# MiniCar_SchDoc.net
KiCad netlist of a schematic drawn in Altium Designer
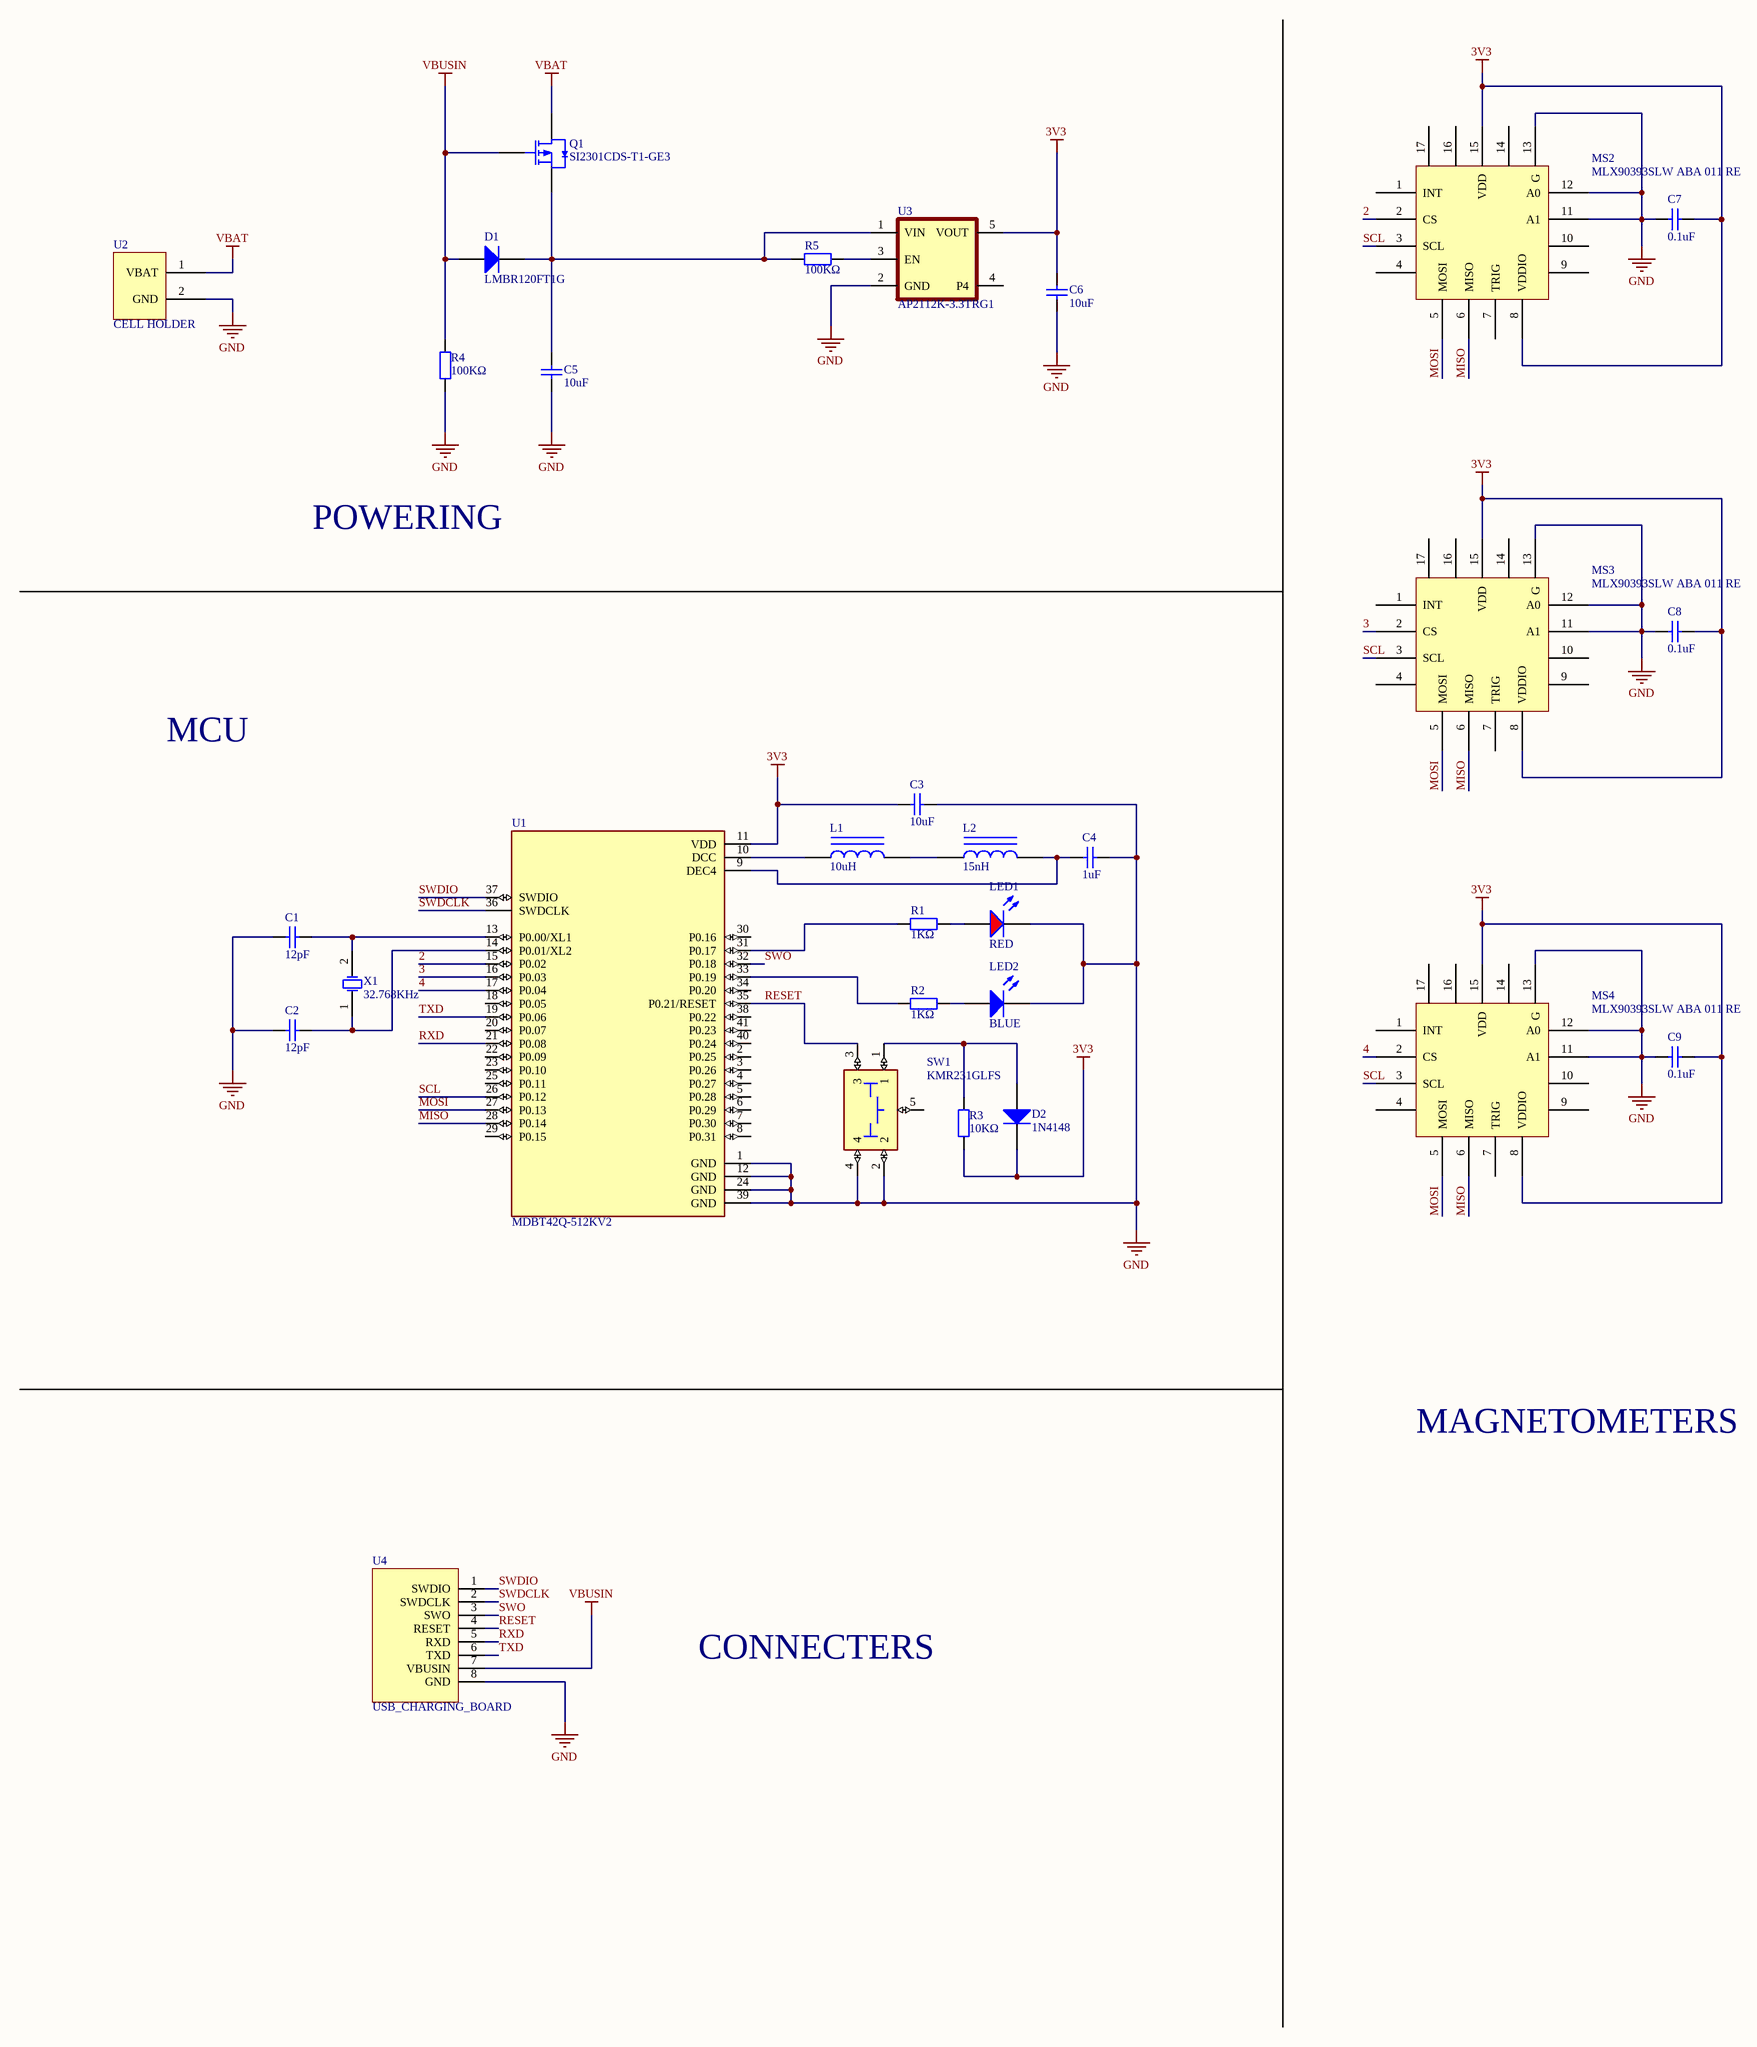
[diagram p0: MiniCar_SchDoc.SchDoc]

(export (version "E")
  (design (tool "Eeschema 10.0.6"))
  (components
    (comp (ref "C1")
      (value "12pF")
      (footprint "0402_C")
      (description "capacitance")
      (libsource (lib "magjoint_MCU") (part "CAP_12pF"))
    )
    (comp (ref "C2")
      (value "12pF")
      (footprint "0402_C")
      (description "capacitance")
      (libsource (lib "magjoint_MCU") (part "CAP_12pF"))
    )
    (comp (ref "C3")
      (value "10uF")
      (footprint "0402_C")
      (description "capacitance")
      (libsource (lib "magjoint_MCU") (part "CAP_10uF"))
    )
    (comp (ref "C4")
      (value "1uF")
      (footprint "0402_C")
      (description "capacitance")
      (libsource (lib "magjoint_MCU") (part "CAP_10uF"))
    )
    (comp (ref "C5")
      (value "10uF")
      (footprint "0402_C")
      (description "capacitance")
      (libsource (lib "magjoint_MCU") (part "CAP_10uF"))
    )
    (comp (ref "C6")
      (value "10uF")
      (footprint "0402_C")
      (description "capacitance")
      (libsource (lib "magjoint_MCU") (part "CAP_10uF"))
    )
    (comp (ref "C7")
      (value "0.1uF")
      (footprint "0402_C")
      (description "capacitance")
      (libsource (lib "magjoint_MCU") (part "CAP_1uF"))
    )
    (comp (ref "C8")
      (value "0.1uF")
      (footprint "0402_C")
      (description "capacitance")
      (libsource (lib "magjoint_MCU") (part "CAP_1uF"))
    )
    (comp (ref "C9")
      (value "0.1uF")
      (footprint "0402_C")
      (description "capacitance")
      (libsource (lib "magjoint_MCU") (part "CAP_1uF"))
    )
    (comp (ref "D1")
      (value "LMBR120FT1G")
      (footprint "SOD-123")
      (description "schottky diode")
      (libsource (lib "magjoint_MCU") (part "DIO_5"))
    )
    (comp (ref "D2")
      (value "1N4148")
      (footprint "SOD-323F")
      (description "diode")
      (libsource (lib "MAGNETO") (part "DIO_4"))
    )
    (comp (ref "L1")
      (value "10uH")
      (footprint "0402_L")
      (description "inductance")
      (libsource (lib "magjoint_MCU") (part "IND_10uH"))
    )
    (comp (ref "L2")
      (value "15nH")
      (footprint "0402_L")
      (description "inductance")
      (libsource (lib "magjoint_MCU") (part "IND_15nH"))
    )
    (comp (ref "LED1")
      (value "RED")
      (footprint "0603_LED_S1")
      (description "LED")
      (libsource (lib "magjoint_MCU") (part "LED_RED"))
    )
    (comp (ref "LED2")
      (value "BLUE")
      (footprint "0603_LED_S1")
      (description "LED")
      (libsource (lib "magjoint_MCU") (part "LED_BLUE"))
    )
    (comp (ref "MS2")
      (value "MLX90393SLW ABA 011 RE")
      (footprint "VQFN-16_EP_3.0x3.0xo.5P")
      (description "sensor")
      (libsource (lib "magjoint_MCU") (part "MLX90393SLW ABA 011 RE"))
    )
    (comp (ref "MS3")
      (value "MLX90393SLW ABA 011 RE")
      (footprint "VQFN-16_EP_3.0x3.0xo.5P")
      (description "sensor")
      (libsource (lib "magjoint_MCU") (part "MLX90393SLW ABA 011 RE"))
    )
    (comp (ref "MS4")
      (value "MLX90393SLW ABA 011 RE")
      (footprint "VQFN-16_EP_3.0x3.0xo.5P")
      (description "sensor")
      (libsource (lib "magjoint_MCU") (part "MLX90393SLW ABA 011 RE"))
    )
    (comp (ref "Q1")
      (value "SI2301CDS-T1-GE3")
      (footprint "SOT-23(SOT-23-3)")
      (description "field effect tube")
      (libsource (lib "magjoint_MCU") (part "MOS"))
    )
    (comp (ref "R1")
      (value "1KΩ")
      (footprint "0402_R")
      (description "resistance")
      (libsource (lib "magjoint_MCU") (part "RES_1KΩ"))
    )
    (comp (ref "R2")
      (value "1KΩ")
      (footprint "0402_R")
      (description "resistance")
      (libsource (lib "magjoint_MCU") (part "RES_1KΩ"))
    )
    (comp (ref "R3")
      (value "10KΩ")
      (footprint "0402_R")
      (description "resistance")
      (libsource (lib "") (part "RES_1KΩ_1"))
    )
    (comp (ref "R4")
      (value "100KΩ")
      (footprint "0402_R")
      (description "resistance")
      (libsource (lib "") (part "RES_100KΩ_1"))
    )
    (comp (ref "R5")
      (value "100KΩ")
      (footprint "0402_R")
      (description "resistance")
      (libsource (lib "magjoint_MCU") (part "RES_100KΩ"))
    )
    (comp (ref "SW1")
      (value "KMR231GLFS")
      (footprint "KMR231GLFS")
      (description "Tactile Switch SPST-NO Top Actuated Surface Mount")
      (libsource (lib "magjoint_MCU") (part "KMR231GLFS"))
    )
    (comp (ref "U1")
      (value "MDBT42Q-512KV2")
      (footprint "SMD_10.0X16.0")
      (libsource (lib "magjoint_MCU") (part "MDBT42Q-512KV2"))
    )
    (comp (ref "U2")
      (value "CELL HOLDER")
      (footprint "BAT_MX 1.25-WI-2P")
      (description "button cell battary holder BS-08-B2AA025")
      (libsource (lib "magjoint_MCU") (part "BAT"))
    )
    (comp (ref "U3")
      (value "AP2112K-3.3TRG1")
      (footprint "SOT95P285X140-5N")
      (description "LDO_ low dropout linear regulator")
      (libsource (lib "magjoint_MCU") (part "AP2112K"))
    )
    (comp (ref "U4")
      (value "USB_CHARGING_BOARD")
      (footprint "FPC0.5 2H-WS-8P")
      (libsource (lib "magjoint_MCU") (part "USB_CHARGING_BOARD"))
    )
    (comp (ref "X1")
      (value "32.768KHz")
      (footprint "SMD-3215_2P FC - 135")
      (description "crystal")
      (libsource (lib "magjoint_MCU") (part "ABS07-32.768KHZ-7-T"))
    )
  )
  (nets
    (net (code "1") (name "/2") (class "Default")
      (node (ref "MS2") (pin "2") (pinfunction "CS_2") (pintype "passive"))
      (node (ref "U1") (pin "15") (pinfunction "P0.02_15") (pintype "bidirectional"))
    )
    (net (code "2") (name "/3") (class "Default")
      (node (ref "MS3") (pin "2") (pinfunction "CS_2") (pintype "passive"))
      (node (ref "U1") (pin "16") (pinfunction "P0.03_16") (pintype "bidirectional"))
    )
    (net (code "3") (name "/4") (class "Default")
      (node (ref "MS4") (pin "2") (pinfunction "CS_2") (pintype "passive"))
      (node (ref "U1") (pin "17") (pinfunction "P0.04_17") (pintype "bidirectional"))
    )
    (net (code "4") (name "/MISO") (class "Default")
      (node (ref "MS2") (pin "6") (pinfunction "MISO_6") (pintype "passive"))
      (node (ref "MS3") (pin "6") (pinfunction "MISO_6") (pintype "passive"))
      (node (ref "MS4") (pin "6") (pinfunction "MISO_6") (pintype "passive"))
      (node (ref "U1") (pin "28") (pinfunction "P0.14_28") (pintype "bidirectional"))
    )
    (net (code "5") (name "/MOSI") (class "Default")
      (node (ref "MS2") (pin "5") (pinfunction "MOSI_5") (pintype "passive"))
      (node (ref "MS3") (pin "5") (pinfunction "MOSI_5") (pintype "passive"))
      (node (ref "MS4") (pin "5") (pinfunction "MOSI_5") (pintype "passive"))
      (node (ref "U1") (pin "27") (pinfunction "P0.13_27") (pintype "bidirectional"))
    )
    (net (code "6") (name "/RESET") (class "Default")
      (node (ref "SW1") (pin "3") (pinfunction "3_3") (pintype "bidirectional"))
      (node (ref "U1") (pin "35") (pinfunction "P0.21/RESET_35") (pintype "bidirectional"))
      (node (ref "U4") (pin "4") (pinfunction "RESET_4") (pintype "passive"))
    )
    (net (code "7") (name "/RXD") (class "Default")
      (node (ref "U1") (pin "21") (pinfunction "P0.08_21") (pintype "bidirectional"))
      (node (ref "U4") (pin "5") (pinfunction "RXD_5") (pintype "passive"))
    )
    (net (code "8") (name "/SCL") (class "Default")
      (node (ref "MS2") (pin "3") (pinfunction "SCL_3") (pintype "passive"))
      (node (ref "MS3") (pin "3") (pinfunction "SCL_3") (pintype "passive"))
      (node (ref "MS4") (pin "3") (pinfunction "SCL_3") (pintype "passive"))
      (node (ref "U1") (pin "26") (pinfunction "P0.12_26") (pintype "bidirectional"))
    )
    (net (code "9") (name "/SWDCLK") (class "Default")
      (node (ref "U1") (pin "36") (pinfunction "SWDCLK_36") (pintype "power_in"))
      (node (ref "U4") (pin "2") (pinfunction "SWDCLK_2") (pintype "passive"))
    )
    (net (code "10") (name "/SWDIO") (class "Default")
      (node (ref "U1") (pin "37") (pinfunction "SWDIO_37") (pintype "bidirectional"))
      (node (ref "U4") (pin "1") (pinfunction "SWDIO_1") (pintype "passive"))
    )
    (net (code "11") (name "/SWO") (class "Default")
      (node (ref "U1") (pin "32") (pinfunction "P0.18_32") (pintype "bidirectional"))
      (node (ref "U4") (pin "3") (pinfunction "SWO_3") (pintype "passive"))
    )
    (net (code "12") (name "/TXD") (class "Default")
      (node (ref "U1") (pin "19") (pinfunction "P0.06_19") (pintype "bidirectional"))
      (node (ref "U4") (pin "6") (pinfunction "TXD_6") (pintype "passive"))
    )
    (net (code "13") (name "3V3") (class "Default")
      (node (ref "C3") (pin "1") (pinfunction "1_1") (pintype "passive"))
      (node (ref "C6") (pin "2") (pinfunction "2_2") (pintype "passive"))
      (node (ref "C7") (pin "2") (pinfunction "2_2") (pintype "passive"))
      (node (ref "C8") (pin "2") (pinfunction "2_2") (pintype "passive"))
      (node (ref "C9") (pin "2") (pinfunction "2_2") (pintype "passive"))
      (node (ref "D2") (pin "2") (pinfunction "K_2") (pintype "passive"))
      (node (ref "MS2") (pin "15") (pinfunction "VDD_15") (pintype "passive"))
      (node (ref "MS2") (pin "8") (pinfunction "VDDIO_8") (pintype "passive"))
      (node (ref "MS3") (pin "15") (pinfunction "VDD_15") (pintype "passive"))
      (node (ref "MS3") (pin "8") (pinfunction "VDDIO_8") (pintype "passive"))
      (node (ref "MS4") (pin "15") (pinfunction "VDD_15") (pintype "passive"))
      (node (ref "MS4") (pin "8") (pinfunction "VDDIO_8") (pintype "passive"))
      (node (ref "R3") (pin "1") (pinfunction "1_1") (pintype "passive"))
      (node (ref "U1") (pin "11") (pinfunction "VDD_11") (pintype "power_in"))
      (node (ref "U3") (pin "5") (pinfunction "VOUT_5") (pintype "power_in"))
    )
    (net (code "14") (name "GND") (class "Default")
      (node (ref "C1") (pin "1") (pinfunction "1_1") (pintype "passive"))
      (node (ref "C2") (pin "1") (pinfunction "1_1") (pintype "passive"))
      (node (ref "C3") (pin "2") (pinfunction "2_2") (pintype "passive"))
      (node (ref "C4") (pin "2") (pinfunction "2_2") (pintype "passive"))
      (node (ref "C5") (pin "1") (pinfunction "1_1") (pintype "passive"))
      (node (ref "C6") (pin "1") (pinfunction "1_1") (pintype "passive"))
      (node (ref "C7") (pin "1") (pinfunction "1_1") (pintype "passive"))
      (node (ref "C8") (pin "1") (pinfunction "1_1") (pintype "passive"))
      (node (ref "C9") (pin "1") (pinfunction "1_1") (pintype "passive"))
      (node (ref "LED1") (pin "K") (pinfunction "K_K") (pintype "passive"))
      (node (ref "LED2") (pin "K") (pinfunction "K_K") (pintype "passive"))
      (node (ref "MS2") (pin "11") (pinfunction "A1_11") (pintype "passive"))
      (node (ref "MS2") (pin "12") (pinfunction "A0_12") (pintype "passive"))
      (node (ref "MS2") (pin "13") (pinfunction "G_13") (pintype "passive"))
      (node (ref "MS3") (pin "11") (pinfunction "A1_11") (pintype "passive"))
      (node (ref "MS3") (pin "12") (pinfunction "A0_12") (pintype "passive"))
      (node (ref "MS3") (pin "13") (pinfunction "G_13") (pintype "passive"))
      (node (ref "MS4") (pin "11") (pinfunction "A1_11") (pintype "passive"))
      (node (ref "MS4") (pin "12") (pinfunction "A0_12") (pintype "passive"))
      (node (ref "MS4") (pin "13") (pinfunction "G_13") (pintype "passive"))
      (node (ref "R4") (pin "1") (pinfunction "1_1") (pintype "passive"))
      (node (ref "SW1") (pin "2") (pinfunction "2_2") (pintype "bidirectional"))
      (node (ref "SW1") (pin "4") (pinfunction "4_4") (pintype "bidirectional"))
      (node (ref "U1") (pin "1") (pinfunction "GND_1") (pintype "power_in"))
      (node (ref "U1") (pin "12") (pinfunction "GND_12") (pintype "power_in"))
      (node (ref "U1") (pin "24") (pinfunction "GND_24") (pintype "power_in"))
      (node (ref "U1") (pin "39") (pinfunction "GND_39") (pintype "power_in"))
      (node (ref "U2") (pin "2") (pinfunction "GND_2") (pintype "passive"))
      (node (ref "U3") (pin "2") (pinfunction "GND_2") (pintype "power_in"))
      (node (ref "U4") (pin "8") (pinfunction "GND_8") (pintype "passive"))
    )
    (net (code "15") (name "Net-(D1-K)") (class "Default")
      (node (ref "C5") (pin "2") (pinfunction "2_2") (pintype "passive"))
      (node (ref "D1") (pin "2") (pinfunction "K_2") (pintype "passive"))
      (node (ref "Q1") (pin "2") (pinfunction "S_2") (pintype "passive"))
      (node (ref "R5") (pin "2") (pinfunction "2_2") (pintype "passive"))
      (node (ref "U3") (pin "1") (pinfunction "VIN_1") (pintype "power_in"))
    )
    (net (code "16") (name "Net-(D2-A)") (class "Default")
      (node (ref "D2") (pin "1") (pinfunction "A_1") (pintype "passive"))
      (node (ref "R3") (pin "2") (pinfunction "2_2") (pintype "passive"))
      (node (ref "SW1") (pin "1") (pinfunction "1_1") (pintype "bidirectional"))
    )
    (net (code "17") (name "Net-(L1-Pad2)") (class "Default")
      (node (ref "L1") (pin "2") (pinfunction "2_2") (pintype "passive"))
      (node (ref "L2") (pin "1") (pinfunction "1_1") (pintype "passive"))
    )
    (net (code "18") (name "Net-(LED1-PadA)") (class "Default")
      (node (ref "LED1") (pin "A") (pinfunction "A_A") (pintype "passive"))
      (node (ref "R1") (pin "2") (pinfunction "2_2") (pintype "passive"))
    )
    (net (code "19") (name "Net-(LED2-PadA)") (class "Default")
      (node (ref "LED2") (pin "A") (pinfunction "A_A") (pintype "passive"))
      (node (ref "R2") (pin "2") (pinfunction "2_2") (pintype "passive"))
    )
    (net (code "20") (name "Net-(U1-DCC)") (class "Default")
      (node (ref "L1") (pin "1") (pinfunction "1_1") (pintype "passive"))
      (node (ref "U1") (pin "10") (pinfunction "DCC_10") (pintype "power_in"))
    )
    (net (code "21") (name "Net-(U1-DEC4)") (class "Default")
      (node (ref "C4") (pin "1") (pinfunction "1_1") (pintype "passive"))
      (node (ref "L2") (pin "2") (pinfunction "2_2") (pintype "passive"))
      (node (ref "U1") (pin "9") (pinfunction "DEC4_9") (pintype "power_in"))
    )
    (net (code "22") (name "Net-(U1-P0.00{slash}XL1)") (class "Default")
      (node (ref "C1") (pin "2") (pinfunction "2_2") (pintype "passive"))
      (node (ref "U1") (pin "13") (pinfunction "P0.00/XL1_13") (pintype "bidirectional"))
      (node (ref "X1") (pin "2") (pinfunction "OSC2_2") (pintype "passive"))
    )
    (net (code "23") (name "Net-(U1-P0.01{slash}XL2)") (class "Default")
      (node (ref "C2") (pin "2") (pinfunction "2_2") (pintype "passive"))
      (node (ref "U1") (pin "14") (pinfunction "P0.01/XL2_14") (pintype "bidirectional"))
      (node (ref "X1") (pin "1") (pinfunction "OSC1_1") (pintype "passive"))
    )
    (net (code "24") (name "Net-(U1-P0.17)") (class "Default")
      (node (ref "R1") (pin "1") (pinfunction "1_1") (pintype "passive"))
      (node (ref "U1") (pin "31") (pinfunction "P0.17_31") (pintype "bidirectional"))
    )
    (net (code "25") (name "Net-(U1-P0.19)") (class "Default")
      (node (ref "R2") (pin "1") (pinfunction "1_1") (pintype "passive"))
      (node (ref "U1") (pin "33") (pinfunction "P0.19_33") (pintype "bidirectional"))
    )
    (net (code "26") (name "Net-(U3-EN)") (class "Default")
      (node (ref "R5") (pin "1") (pinfunction "1_1") (pintype "passive"))
      (node (ref "U3") (pin "3") (pinfunction "EN_3") (pintype "power_in"))
    )
    (net (code "27") (name "VBAT") (class "Default")
      (node (ref "Q1") (pin "3") (pinfunction "D_3") (pintype "passive"))
      (node (ref "U2") (pin "1") (pinfunction "VBAT_1") (pintype "passive"))
    )
    (net (code "28") (name "VBUSIN") (class "Default")
      (node (ref "D1") (pin "1") (pinfunction "A_1") (pintype "passive"))
      (node (ref "Q1") (pin "1") (pinfunction "G_1") (pintype "passive"))
      (node (ref "R4") (pin "2") (pinfunction "2_2") (pintype "passive"))
      (node (ref "U4") (pin "7") (pinfunction "VBUSIN_7") (pintype "passive"))
    )
    (net (code "29") (name "unconnected-(MS2-INT-Pad1)") (class "Default")
      (node (ref "MS2") (pin "1") (pinfunction "INT_1") (pintype "passive"))
    )
    (net (code "30") (name "unconnected-(MS2-Pad4)") (class "Default")
      (node (ref "MS2") (pin "4") (pintype "passive"))
    )
    (net (code "31") (name "unconnected-(MS2-Pad9)") (class "Default")
      (node (ref "MS2") (pin "9") (pintype "passive"))
    )
    (net (code "32") (name "unconnected-(MS2-Pad10)") (class "Default")
      (node (ref "MS2") (pin "10") (pintype "passive"))
    )
    (net (code "33") (name "unconnected-(MS2-Pad14)") (class "Default")
      (node (ref "MS2") (pin "14") (pintype "passive"))
    )
    (net (code "34") (name "unconnected-(MS2-Pad16)") (class "Default")
      (node (ref "MS2") (pin "16") (pintype "passive"))
    )
    (net (code "35") (name "unconnected-(MS2-Pad17)") (class "Default")
      (node (ref "MS2") (pin "17") (pintype "passive"))
    )
    (net (code "36") (name "unconnected-(MS2-TRIG-Pad7)") (class "Default")
      (node (ref "MS2") (pin "7") (pinfunction "TRIG_7") (pintype "passive"))
    )
    (net (code "37") (name "unconnected-(MS3-INT-Pad1)") (class "Default")
      (node (ref "MS3") (pin "1") (pinfunction "INT_1") (pintype "passive"))
    )
    (net (code "38") (name "unconnected-(MS3-Pad4)") (class "Default")
      (node (ref "MS3") (pin "4") (pintype "passive"))
    )
    (net (code "39") (name "unconnected-(MS3-Pad9)") (class "Default")
      (node (ref "MS3") (pin "9") (pintype "passive"))
    )
    (net (code "40") (name "unconnected-(MS3-Pad10)") (class "Default")
      (node (ref "MS3") (pin "10") (pintype "passive"))
    )
    (net (code "41") (name "unconnected-(MS3-Pad14)") (class "Default")
      (node (ref "MS3") (pin "14") (pintype "passive"))
    )
    (net (code "42") (name "unconnected-(MS3-Pad16)") (class "Default")
      (node (ref "MS3") (pin "16") (pintype "passive"))
    )
    (net (code "43") (name "unconnected-(MS3-Pad17)") (class "Default")
      (node (ref "MS3") (pin "17") (pintype "passive"))
    )
    (net (code "44") (name "unconnected-(MS3-TRIG-Pad7)") (class "Default")
      (node (ref "MS3") (pin "7") (pinfunction "TRIG_7") (pintype "passive"))
    )
    (net (code "45") (name "unconnected-(MS4-INT-Pad1)") (class "Default")
      (node (ref "MS4") (pin "1") (pinfunction "INT_1") (pintype "passive"))
    )
    (net (code "46") (name "unconnected-(MS4-Pad4)") (class "Default")
      (node (ref "MS4") (pin "4") (pintype "passive"))
    )
    (net (code "47") (name "unconnected-(MS4-Pad9)") (class "Default")
      (node (ref "MS4") (pin "9") (pintype "passive"))
    )
    (net (code "48") (name "unconnected-(MS4-Pad10)") (class "Default")
      (node (ref "MS4") (pin "10") (pintype "passive"))
    )
    (net (code "49") (name "unconnected-(MS4-Pad14)") (class "Default")
      (node (ref "MS4") (pin "14") (pintype "passive"))
    )
    (net (code "50") (name "unconnected-(MS4-Pad16)") (class "Default")
      (node (ref "MS4") (pin "16") (pintype "passive"))
    )
    (net (code "51") (name "unconnected-(MS4-Pad17)") (class "Default")
      (node (ref "MS4") (pin "17") (pintype "passive"))
    )
    (net (code "52") (name "unconnected-(MS4-TRIG-Pad7)") (class "Default")
      (node (ref "MS4") (pin "7") (pinfunction "TRIG_7") (pintype "passive"))
    )
    (net (code "53") (name "unconnected-(SW1-Pad5)") (class "Default")
      (node (ref "SW1") (pin "5") (pinfunction "5_5") (pintype "bidirectional"))
    )
    (net (code "54") (name "unconnected-(U1-P0.05-Pad18)") (class "Default")
      (node (ref "U1") (pin "18") (pinfunction "P0.05_18") (pintype "bidirectional"))
    )
    (net (code "55") (name "unconnected-(U1-P0.07-Pad20)") (class "Default")
      (node (ref "U1") (pin "20") (pinfunction "P0.07_20") (pintype "bidirectional"))
    )
    (net (code "56") (name "unconnected-(U1-P0.09-Pad22)") (class "Default")
      (node (ref "U1") (pin "22") (pinfunction "P0.09_22") (pintype "bidirectional"))
    )
    (net (code "57") (name "unconnected-(U1-P0.10-Pad23)") (class "Default")
      (node (ref "U1") (pin "23") (pinfunction "P0.10_23") (pintype "bidirectional"))
    )
    (net (code "58") (name "unconnected-(U1-P0.11-Pad25)") (class "Default")
      (node (ref "U1") (pin "25") (pinfunction "P0.11_25") (pintype "bidirectional"))
    )
    (net (code "59") (name "unconnected-(U1-P0.15-Pad29)") (class "Default")
      (node (ref "U1") (pin "29") (pinfunction "P0.15_29") (pintype "bidirectional"))
    )
    (net (code "60") (name "unconnected-(U1-P0.16-Pad30)") (class "Default")
      (node (ref "U1") (pin "30") (pinfunction "P0.16_30") (pintype "bidirectional"))
    )
    (net (code "61") (name "unconnected-(U1-P0.20-Pad34)") (class "Default")
      (node (ref "U1") (pin "34") (pinfunction "P0.20_34") (pintype "bidirectional"))
    )
    (net (code "62") (name "unconnected-(U1-P0.22-Pad38)") (class "Default")
      (node (ref "U1") (pin "38") (pinfunction "P0.22_38") (pintype "bidirectional"))
    )
    (net (code "63") (name "unconnected-(U1-P0.23-Pad41)") (class "Default")
      (node (ref "U1") (pin "41") (pinfunction "P0.23_41") (pintype "bidirectional"))
    )
    (net (code "64") (name "unconnected-(U1-P0.24-Pad40)") (class "Default")
      (node (ref "U1") (pin "40") (pinfunction "P0.24_40") (pintype "bidirectional"))
    )
    (net (code "65") (name "unconnected-(U1-P0.25-Pad2)") (class "Default")
      (node (ref "U1") (pin "2") (pinfunction "P0.25_2") (pintype "bidirectional"))
    )
    (net (code "66") (name "unconnected-(U1-P0.26-Pad3)") (class "Default")
      (node (ref "U1") (pin "3") (pinfunction "P0.26_3") (pintype "bidirectional"))
    )
    (net (code "67") (name "unconnected-(U1-P0.27-Pad4)") (class "Default")
      (node (ref "U1") (pin "4") (pinfunction "P0.27_4") (pintype "bidirectional"))
    )
    (net (code "68") (name "unconnected-(U1-P0.28-Pad5)") (class "Default")
      (node (ref "U1") (pin "5") (pinfunction "P0.28_5") (pintype "bidirectional"))
    )
    (net (code "69") (name "unconnected-(U1-P0.29-Pad6)") (class "Default")
      (node (ref "U1") (pin "6") (pinfunction "P0.29_6") (pintype "bidirectional"))
    )
    (net (code "70") (name "unconnected-(U1-P0.30-Pad7)") (class "Default")
      (node (ref "U1") (pin "7") (pinfunction "P0.30_7") (pintype "bidirectional"))
    )
    (net (code "71") (name "unconnected-(U1-P0.31-Pad8)") (class "Default")
      (node (ref "U1") (pin "8") (pinfunction "P0.31_8") (pintype "bidirectional"))
    )
    (net (code "72") (name "unconnected-(U3-P4-Pad4)") (class "Default")
      (node (ref "U3") (pin "4") (pinfunction "P4_4") (pintype "power_in"))
    )
  )
)
